# MCU.net
KiCad netlist of a schematic drawn in Altium Designer
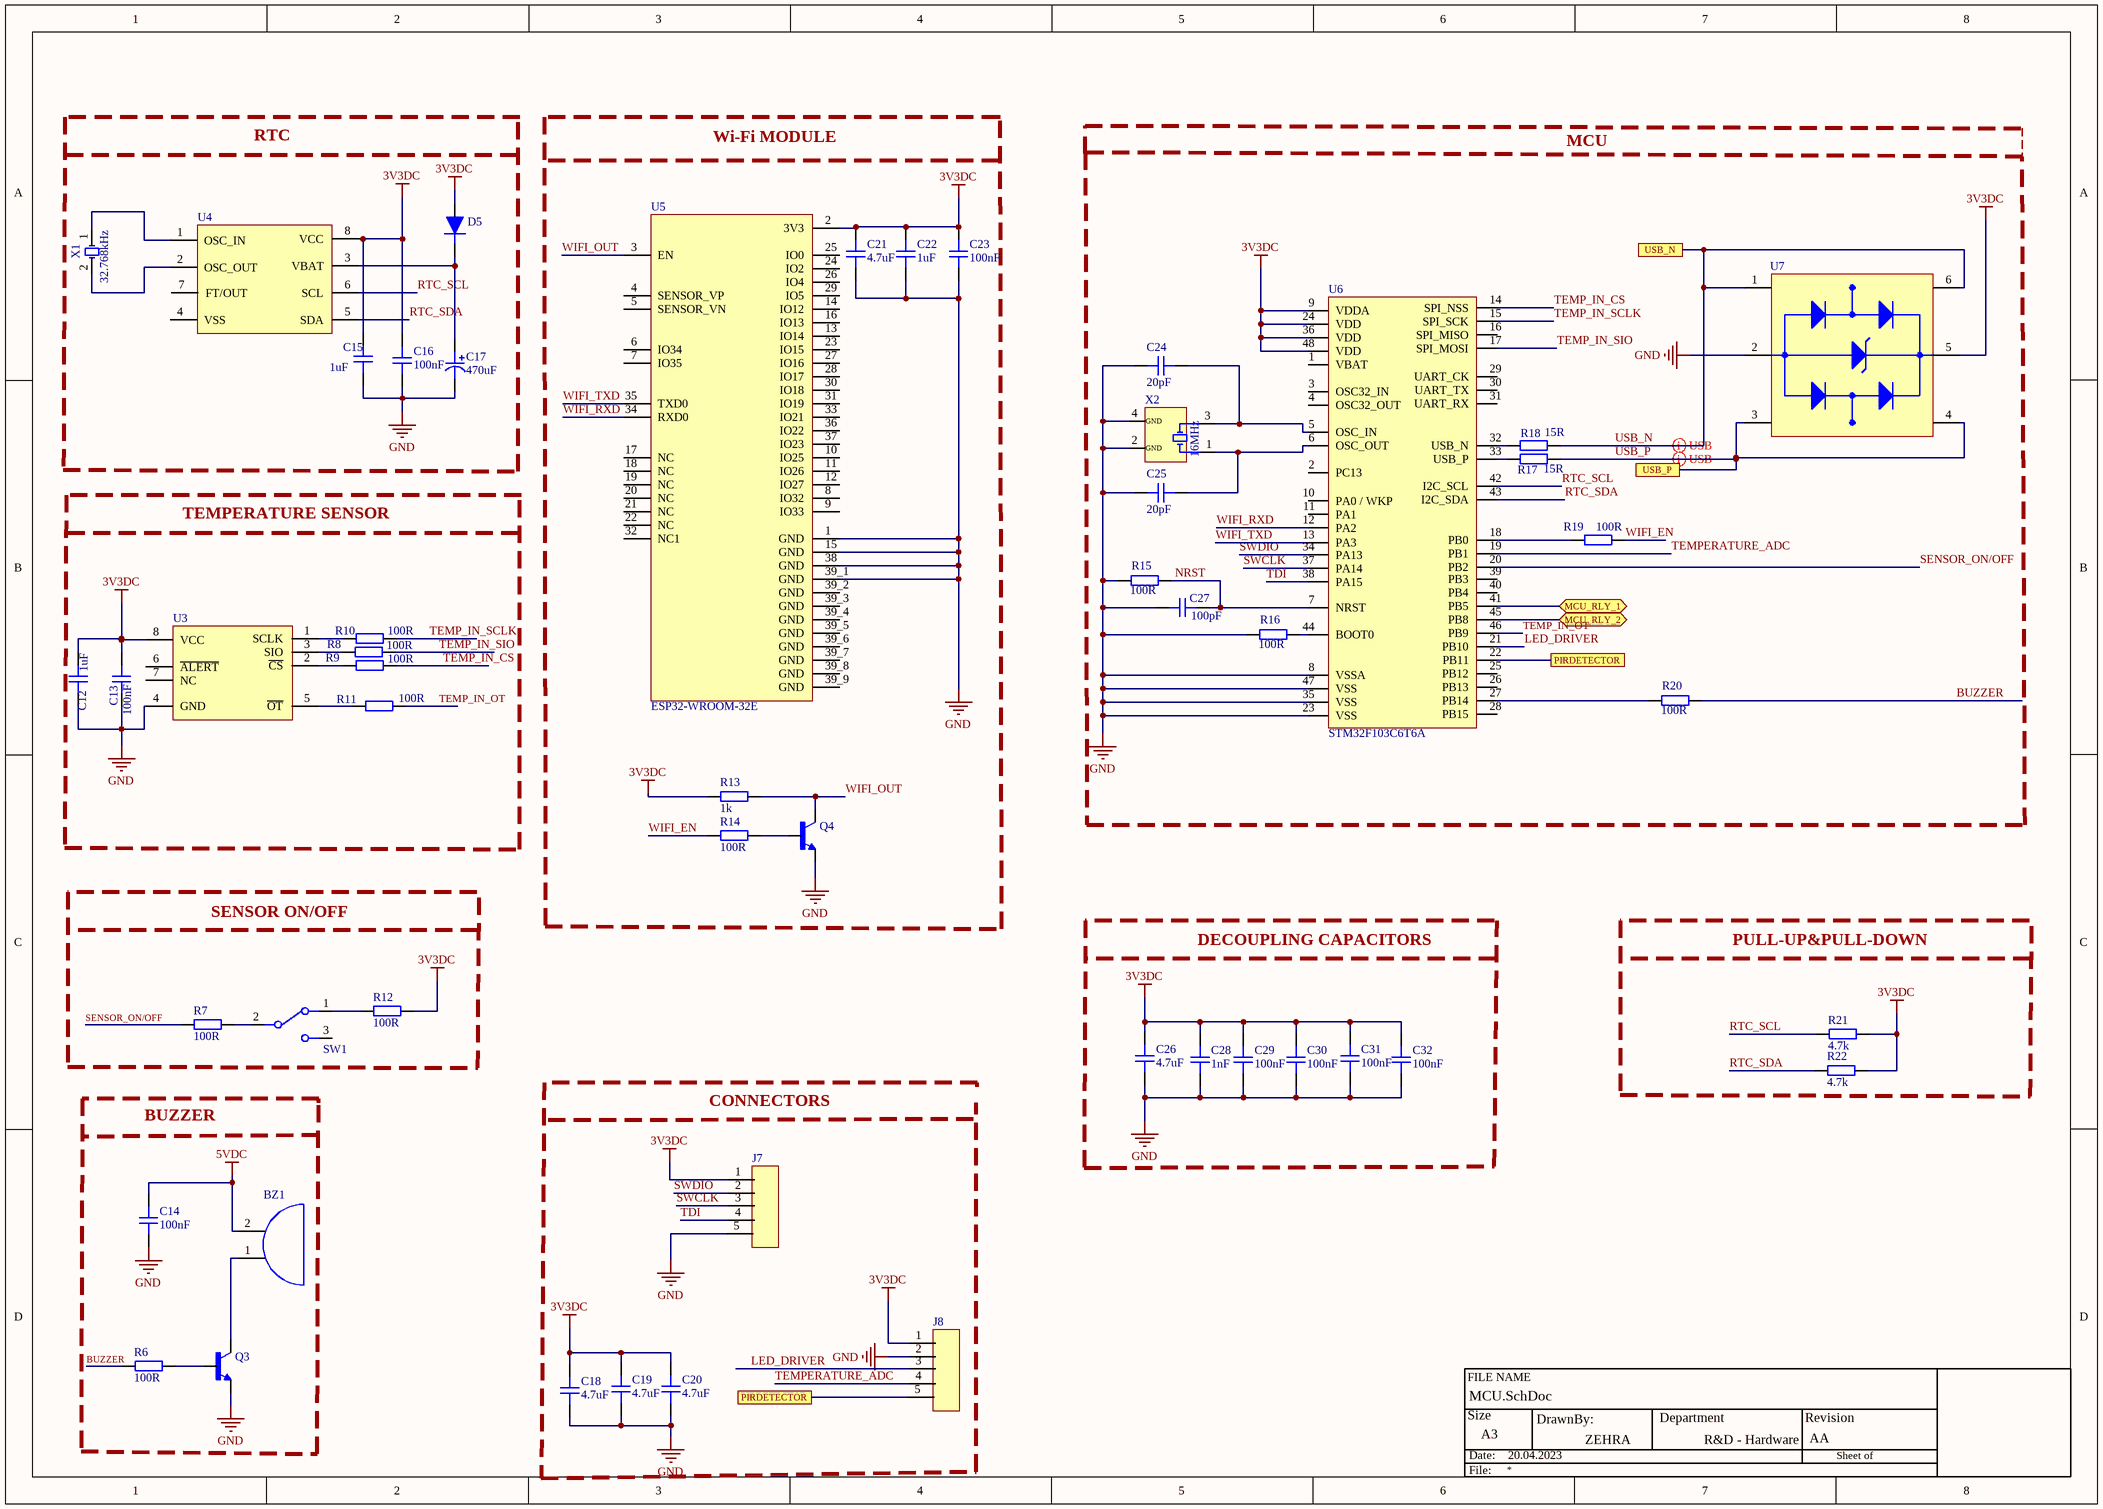
[diagram p0: MCU.SchDoc]

(export (version "E")
  (design (tool "Eeschema 10.0.6"))
  (components
    (comp (ref "BZ1")
      (value "CMI-9605IC-0580T")
      (footprint "CMI-9605IC-0580T")
      (description "Audio Buzzer Magnetic 3VDC 7VDC 30mA 5VDC 85dB 2600Hz to 2800Hz Through Hole Pin Box")
      (fields (field (name "MANUFACTURER") "CUI Devices") (field (name "DESIGNER") "ZehraOzkan"))
      (libsource (lib "Integrated_Library1") (part "CMI-9605IC-0580T"))
    )
    (comp (ref "C12")
      (value "1uF")
      (footprint "CAP_0805")
      (description "Capacitor SMD 0805 10V")
      (fields (field (name "DESIGNER") "ZehraOzkan"))
      (libsource (lib "Integrated_Library1") (part "CAP_0805_10V"))
    )
    (comp (ref "C13")
      (value "100nF")
      (footprint "CAP_0805")
      (description "Capacitor SMD 0805 10V")
      (fields (field (name "DESIGNER") "ZehraOzkan"))
      (libsource (lib "Integrated_Library1") (part "CAP_0805_10V"))
    )
    (comp (ref "C14")
      (value "100nF")
      (footprint "CAP_0805")
      (description "Capacitor SMD 0805 10V")
      (fields (field (name "DESIGNER") "ZehraOzkan"))
      (libsource (lib "Integrated_Library1") (part "CAP_0805_10V"))
    )
    (comp (ref "C15")
      (value "1uF")
      (footprint "CAP_0805")
      (description "Capacitor SMD 0805 10V")
      (fields (field (name "DESIGNER") "ZehraOzkan"))
      (libsource (lib "Integrated_Library1") (part "CAP_0805_10V"))
    )
    (comp (ref "C16")
      (value "100nF")
      (footprint "CAP_0805")
      (description "Capacitor SMD 0805 10V")
      (fields (field (name "DESIGNER") "ZehraOzkan"))
      (libsource (lib "Integrated_Library1") (part "CAP_0805_10V"))
    )
    (comp (ref "C17")
      (value "470uF")
      (footprint "CAP_EEVSERIES")
      (description "Cap Aluminum Lytic 68uF 25V 20% (6.3 X 5.4mm) SMD 240mA 2000h 105C T/R")
      (fields
        (field (name "MANUFACTURER") "KEMET")
        (field (name "MANUFACTURER PART NUMBER") "EEV686M025A9GAA")
        (field (name "DESIGNER") "ZehraOzkan")
      )
      (libsource (lib "Integrated_Library1") (part "CAP_ALU_68uF"))
    )
    (comp (ref "C18")
      (value "4.7uF")
      (footprint "CAP_0603")
      (description "Capacitor SMD 0603 10V")
      (libsource (lib "Integrated_Library1") (part "CAP_0603_10V"))
    )
    (comp (ref "C19")
      (value "4.7uF")
      (footprint "CAP_0603")
      (description "Capacitor SMD 0603 10V")
      (libsource (lib "Integrated_Library1") (part "CAP_0603_10V"))
    )
    (comp (ref "C20")
      (value "4.7uF")
      (footprint "CAP_0603")
      (description "Capacitor SMD 0603 10V")
      (libsource (lib "Integrated_Library1") (part "CAP_0603_10V"))
    )
    (comp (ref "C21")
      (value "4.7uF")
      (footprint "CAP_0805")
      (description "Capacitor SMD 0805 10V")
      (fields (field (name "DESIGNER") "ZehraOzkan"))
      (libsource (lib "Integrated_Library1") (part "CAP_0805_10V"))
    )
    (comp (ref "C22")
      (value "1uF")
      (footprint "CAP_0805")
      (description "Capacitor SMD 0805 10V")
      (fields (field (name "DESIGNER") "ZehraOzkan"))
      (libsource (lib "Integrated_Library1") (part "CAP_0805_10V"))
    )
    (comp (ref "C23")
      (value "100nF")
      (footprint "CAP_0805")
      (description "Capacitor SMD 0805 10V")
      (fields (field (name "DESIGNER") "ZehraOzkan"))
      (libsource (lib "Integrated_Library1") (part "CAP_0805_10V"))
    )
    (comp (ref "C24")
      (value "20pF")
      (footprint "CAP_0603")
      (description "Capacitor SMD 0603 10V")
      (libsource (lib "Integrated_Library1") (part "CAP_0603_10V"))
    )
    (comp (ref "C25")
      (value "20pF")
      (footprint "CAP_0603")
      (description "Capacitor SMD 0603 10V")
      (libsource (lib "Integrated_Library1") (part "CAP_0603_10V"))
    )
    (comp (ref "C26")
      (value "4.7uF")
      (footprint "CAP_0603")
      (description "Capacitor SMD 0603 10V")
      (libsource (lib "Integrated_Library1") (part "CAP_0603_10V"))
    )
    (comp (ref "C27")
      (value "100pF")
      (footprint "CAP_0603")
      (description "Capacitor SMD 0603 10V")
      (libsource (lib "Integrated_Library1") (part "CAP_0603_10V"))
    )
    (comp (ref "C28")
      (value "1nF")
      (footprint "CAP_0603")
      (description "Capacitor SMD 0603 10V")
      (libsource (lib "Integrated_Library1") (part "CAP_0603_10V"))
    )
    (comp (ref "C29")
      (value "100nF")
      (footprint "CAP_0603")
      (description "Capacitor SMD 0603 10V")
      (libsource (lib "Integrated_Library1") (part "CAP_0603_10V"))
    )
    (comp (ref "C30")
      (value "100nF")
      (footprint "CAP_0603")
      (description "Capacitor SMD 0603 10V")
      (libsource (lib "Integrated_Library1") (part "CAP_0603_10V"))
    )
    (comp (ref "C31")
      (value "100nF")
      (footprint "CAP_0603")
      (description "Capacitor SMD 0603 10V")
      (libsource (lib "Integrated_Library1") (part "CAP_0603_10V"))
    )
    (comp (ref "C32")
      (value "100nF")
      (footprint "CAP_0603")
      (description "Capacitor SMD 0603 10V")
      (libsource (lib "Integrated_Library1") (part "CAP_0603_10V"))
    )
    (comp (ref "D5")
      (value "1N5824")
      (footprint "1N5824")
      (description "Diode Schottky 30V 5A 2-Pin Axial Leaded Tray")
      (fields (field (name "MANUFACTURER") "Microsemi") (field (name "DESIGNER") "ZehraOzkan"))
      (libsource (lib "Integrated_Library1") (part "1N5824"))
    )
    (comp (ref "J7")
      (value "Terminal_Block_Header")
      (footprint "HEADER_5")
      (description "5 pin Female")
      (fields (field (name "DESIGNER") "ZehraOzkan"))
      (libsource (lib "Integrated_Library1") (part "Terminal_Block_Header"))
    )
    (comp (ref "J8")
      (value "Terminal_Block_Header")
      (footprint "HEADER_5")
      (description "5 pin Female")
      (fields (field (name "DESIGNER") "ZehraOzkan"))
      (libsource (lib "Integrated_Library1") (part "Terminal_Block_Header"))
    )
    (comp (ref "Q3")
      (value "BC237")
      (footprint "BC237")
      (description "Transistor NPN BC237B MOTOROLA milliampere=100 V=45 R204")
      (fields
        (field (name "MANUFACTURER") "ON Semiconductor / Fairchild")
        (field (name "MANUFACTURER PART NUMBER") "BC237B")
        (field (name "DESIGNER") "ZehraOzkan")
      )
      (libsource (lib "Integrated_Library1") (part "BC237"))
    )
    (comp (ref "Q4")
      (value "BC237")
      (footprint "BC237")
      (description "Transistor NPN BC237B MOTOROLA milliampere=100 V=45 R204")
      (fields
        (field (name "MANUFACTURER") "ON Semiconductor / Fairchild")
        (field (name "MANUFACTURER PART NUMBER") "BC237B")
        (field (name "DESIGNER") "ZehraOzkan")
      )
      (libsource (lib "Integrated_Library1") (part "BC237"))
    )
    (comp (ref "R6")
      (value "100R")
      (footprint "RES_0805")
      (description "Resistor SMD 0805")
      (fields (field (name "DESIGNER") "ZehraOzkan"))
      (libsource (lib "Integrated_Library1") (part "RES_0805"))
    )
    (comp (ref "R7")
      (value "100R")
      (footprint "RES_0805")
      (description "Resistor SMD 0805")
      (fields (field (name "DESIGNER") "ZehraOzkan"))
      (libsource (lib "Integrated_Library1") (part "RES_0805"))
    )
    (comp (ref "R8")
      (value "100R")
      (footprint "RES_0805")
      (description "Resistor SMD 0805")
      (fields (field (name "DESIGNER") "ZehraOzkan"))
      (libsource (lib "Integrated_Library1") (part "RES_0805"))
    )
    (comp (ref "R9")
      (value "100R")
      (footprint "RES_0805")
      (description "Resistor SMD 0805")
      (fields (field (name "DESIGNER") "ZehraOzkan"))
      (libsource (lib "Integrated_Library1") (part "RES_0805"))
    )
    (comp (ref "R10")
      (value "100R")
      (footprint "RES_0805")
      (description "Resistor SMD 0805")
      (fields (field (name "DESIGNER") "ZehraOzkan"))
      (libsource (lib "Integrated_Library1") (part "RES_0805"))
    )
    (comp (ref "R11")
      (value "100R")
      (footprint "RES_0805")
      (description "Resistor SMD 0805")
      (fields (field (name "DESIGNER") "ZehraOzkan"))
      (libsource (lib "Integrated_Library1") (part "RES_0805"))
    )
    (comp (ref "R12")
      (value "100R")
      (footprint "RES_0805")
      (description "Resistor SMD 0805")
      (fields (field (name "DESIGNER") "ZehraOzkan"))
      (libsource (lib "Integrated_Library1") (part "RES_0805"))
    )
    (comp (ref "R13")
      (value "1k")
      (footprint "RES_0805")
      (description "Resistor SMD 0805")
      (fields (field (name "DESIGNER") "ZehraOzkan"))
      (libsource (lib "Integrated_Library1") (part "RES_0805"))
    )
    (comp (ref "R14")
      (value "100R")
      (footprint "RES_0805")
      (description "Resistor SMD 0805")
      (fields (field (name "DESIGNER") "ZehraOzkan"))
      (libsource (lib "Integrated_Library1") (part "RES_0805"))
    )
    (comp (ref "R15")
      (value "100R")
      (footprint "RES_0805")
      (description "Resistor SMD 0805")
      (fields (field (name "DESIGNER") "ZehraOzkan"))
      (libsource (lib "Integrated_Library1") (part "RES_0805"))
    )
    (comp (ref "R16")
      (value "100R")
      (footprint "RES_0805")
      (description "Resistor SMD 0805")
      (fields (field (name "DESIGNER") "ZehraOzkan"))
      (libsource (lib "Integrated_Library1") (part "RES_0805"))
    )
    (comp (ref "R17")
      (value "15R")
      (footprint "RES_0805")
      (description "Resistor SMD 0805")
      (fields (field (name "DESIGNER") "ZehraOzkan"))
      (libsource (lib "Integrated_Library1") (part "RES_0805"))
    )
    (comp (ref "R18")
      (value "15R")
      (footprint "RES_0805")
      (description "Resistor SMD 0805")
      (fields (field (name "DESIGNER") "ZehraOzkan"))
      (libsource (lib "Integrated_Library1") (part "RES_0805"))
    )
    (comp (ref "R19")
      (value "100R")
      (footprint "RES_0805")
      (description "Resistor SMD 0805")
      (fields (field (name "DESIGNER") "ZehraOzkan"))
      (libsource (lib "Integrated_Library1") (part "RES_0805"))
    )
    (comp (ref "R20")
      (value "100R")
      (footprint "RES_0805")
      (description "Resistor SMD 0805")
      (fields (field (name "DESIGNER") "ZehraOzkan"))
      (libsource (lib "Integrated_Library1") (part "RES_0805"))
    )
    (comp (ref "R21")
      (value "4.7k")
      (footprint "RES_0805")
      (description "Resistor SMD 0805")
      (fields (field (name "DESIGNER") "ZehraOzkan"))
      (libsource (lib "Integrated_Library1") (part "RES_0805"))
    )
    (comp (ref "R22")
      (value "4.7k")
      (footprint "RES_0805")
      (description "Resistor SMD 0805")
      (fields (field (name "DESIGNER") "ZehraOzkan"))
      (libsource (lib "Integrated_Library1") (part "RES_0805"))
    )
    (comp (ref "SW1")
      (value "OS102011MA1QN1")
      (footprint "SWITCH")
      (fields (field (name "DESIGNER") "ZehraOzkan"))
      (libsource (lib "Integrated_Library1") (part "Switch"))
    )
    (comp (ref "U3")
      (value "MAX6662")
      (footprint "SOIC-8")
      (description "Temp Sensor Digital Serial (3-Wire, SPI) 8-Pin SOIC N Tube")
      (fields
        (field (name "MANUFACTURER") "Maxim")
        (field (name "MANUFACTURER PART NUMBER") "MAX6662MSA+")
        (field (name "DESIGNER") "ZehraOzkan")
      )
      (libsource (lib "Integrated_Library1") (part "MAX6662"))
    )
    (comp (ref "U4")
      (value "M41T00")
      (footprint "SOIC-8")
      (description "Real-time Clocks Clock/Calendar I2C, 2-Wire Serial 70uA @ 2V ~ 5.5V SOIC-8_150mil RoHS")
      (fields
        (field (name "MANUFACTURER") "STMicroelectronics")
        (field (name "MANUFACTURER PART NUMBER") "M41T00M6F")
        (field (name "DESIGNER") "ZehraOzkan")
      )
      (libsource (lib "Integrated_Library1") (part "M41T00M6F"))
    )
    (comp (ref "U5")
      (value "ESP32-WROOM-32E")
      (footprint "ESP32-WROOM-32E")
      (fields (field (name "MANUFACTURER") "Espressif") (field (name "DESIGNER") "ZehraOzkan"))
      (libsource (lib "Integrated_Library1") (part "ESP32-WROOM-32E"))
    )
    (comp (ref "U6")
      (value "STM32F103C6T6A")
      (footprint "LQFP-48")
      (description "MCU 32-bit STM32F ARM Cortex M3 RISC 32KB Flash 2.5V/3.3V 48-Pin LQFP Tray")
      (fields (field (name "MANUFACTURER") "STMicroelectronics") (field (name "DESIGNER") "ZehraOzkan"))
      (libsource (lib "Integrated_Library1") (part "STM32F103C6T6A"))
    )
    (comp (ref "U7")
      (value "USBLC6-2SC6")
      (footprint "SOT23-6L")
      (description "TVS DIODE 5.25VWM 17VC SOT23-6")
      (fields (field (name "MANUFACTURER") "STMicroelectronics") (field (name "DESIGNER") "ZehraOzkan"))
      (libsource (lib "Integrated_Library1") (part "USB PROTECTION"))
    )
    (comp (ref "X1")
      (value "32.768kHz")
      (footprint "ABS05")
      (description "Crystal 0.032768MHz ±20ppm (Tol) 12.5pF Flexural 90000Ohm 2-Pin CSMD T/R")
      (fields
        (field (name "MANUFACTURER") "Abracon")
        (field (name "MANUFACTURER PART NUMBER") "ABS05-32.768KHZ-T")
        (field (name "DESIGNER") "ZehraOzkan")
      )
      (libsource (lib "Integrated_Library1") (part "Crystal 32768kHz"))
    )
    (comp (ref "X2")
      (value "ECS-160-20-30B-TR")
      (footprint "ECS")
      (description "Crystal 16MHz ±30ppm (Tol) ±50ppm (Stability) 20pF FUND 50Ohm 4-Pin Mini-SMD T/R")
      (fields
        (field (name "MANUFACTURER") "ECS International")
        (field (name "TOLERANCE") "50ppm")
        (field (name "FREQUENCY") "16MHz")
        (field (name "DESIGNER") "ZehraOzkan")
      )
      (libsource (lib "Integrated_Library1") (part "Crystal 16MHz"))
    )
  )
  (nets
    (net (code "1") (name "/BUZZER") (class "Default")
      (node (ref "R20") (pin "2") (pinfunction "2_2") (pintype "passive"))
      (node (ref "R6") (pin "1") (pinfunction "1_1") (pintype "passive"))
    )
    (net (code "2") (name "/LED_DRIVER") (class "Default")
      (node (ref "J8") (pin "3") (pinfunction "3_3") (pintype "passive"))
      (node (ref "U6") (pin "21") (pinfunction "PB10_21") (pintype "passive"))
    )
    (net (code "3") (name "/MCU_RLY_1") (class "Default")
      (node (ref "U6") (pin "41") (pinfunction "PB5_41") (pintype "passive"))
    )
    (net (code "4") (name "/MCU_RLY_2") (class "Default")
      (node (ref "U6") (pin "45") (pinfunction "PB8_45") (pintype "passive"))
    )
    (net (code "5") (name "/NRST") (class "Default")
      (node (ref "C27") (pin "2") (pinfunction "2_2") (pintype "passive"))
      (node (ref "R15") (pin "2") (pinfunction "2_2") (pintype "passive"))
      (node (ref "U6") (pin "7") (pinfunction "NRST_7") (pintype "passive"))
    )
    (net (code "6") (name "/PIRDETECTOR") (class "Default")
      (node (ref "J8") (pin "5") (pinfunction "5_5") (pintype "passive"))
      (node (ref "U6") (pin "22") (pinfunction "PB11_22") (pintype "passive"))
    )
    (net (code "7") (name "/RTC_SCL") (class "Default")
      (node (ref "R21") (pin "1") (pinfunction "1_1") (pintype "passive"))
      (node (ref "U4") (pin "6") (pinfunction "SCL_6") (pintype "passive"))
      (node (ref "U6") (pin "42") (pinfunction "I2C_SCL_42") (pintype "passive"))
    )
    (net (code "8") (name "/RTC_SDA") (class "Default")
      (node (ref "R22") (pin "1") (pinfunction "1_1") (pintype "passive"))
      (node (ref "U4") (pin "5") (pinfunction "SDA_5") (pintype "passive"))
      (node (ref "U6") (pin "43") (pinfunction "I2C_SDA_43") (pintype "passive"))
    )
    (net (code "9") (name "/SENSOR_ON{slash}OFF") (class "Default")
      (node (ref "R7") (pin "1") (pinfunction "1_1") (pintype "passive"))
      (node (ref "U6") (pin "20") (pinfunction "PB2_20") (pintype "passive"))
    )
    (net (code "10") (name "/SWCLK") (class "Default")
      (node (ref "J7") (pin "3") (pinfunction "3_3") (pintype "passive"))
      (node (ref "U6") (pin "37") (pinfunction "PA14_37") (pintype "passive"))
    )
    (net (code "11") (name "/SWDIO") (class "Default")
      (node (ref "J7") (pin "2") (pinfunction "2_2") (pintype "passive"))
      (node (ref "U6") (pin "34") (pinfunction "PA13_34") (pintype "passive"))
    )
    (net (code "12") (name "/TDI") (class "Default")
      (node (ref "J7") (pin "4") (pinfunction "4_4") (pintype "passive"))
      (node (ref "U6") (pin "38") (pinfunction "PA15_38") (pintype "passive"))
    )
    (net (code "13") (name "/TEMPERATURE_ADC") (class "Default")
      (node (ref "J8") (pin "4") (pinfunction "4_4") (pintype "passive"))
      (node (ref "U6") (pin "19") (pinfunction "PB1_19") (pintype "passive"))
    )
    (net (code "14") (name "/TEMP_IN_CS") (class "Default")
      (node (ref "R9") (pin "2") (pinfunction "2_2") (pintype "passive"))
      (node (ref "U6") (pin "14") (pinfunction "SPI_NSS_14") (pintype "passive"))
    )
    (net (code "15") (name "/TEMP_IN_OT") (class "Default")
      (node (ref "R11") (pin "2") (pinfunction "2_2") (pintype "passive"))
      (node (ref "U6") (pin "46") (pinfunction "PB9_46") (pintype "passive"))
    )
    (net (code "16") (name "/TEMP_IN_SCLK") (class "Default")
      (node (ref "R10") (pin "2") (pinfunction "2_2") (pintype "passive"))
      (node (ref "U6") (pin "15") (pinfunction "SPI_SCK_15") (pintype "passive"))
    )
    (net (code "17") (name "/TEMP_IN_SIO") (class "Default")
      (node (ref "R8") (pin "2") (pinfunction "2_2") (pintype "passive"))
      (node (ref "U6") (pin "17") (pinfunction "SPI_MOSI_17") (pintype "passive"))
    )
    (net (code "18") (name "/USB_N") (class "Default")
      (node (ref "R18") (pin "2") (pinfunction "2_2") (pintype "passive"))
      (node (ref "U7") (pin "1") (pinfunction "I/O1_IN_1") (pintype "passive"))
      (node (ref "U7") (pin "6") (pinfunction "I/O1_OUT_6") (pintype "passive"))
    )
    (net (code "19") (name "/USB_P") (class "Default")
      (node (ref "R17") (pin "2") (pinfunction "2_2") (pintype "passive"))
      (node (ref "U7") (pin "3") (pinfunction "I/O2_IN_3") (pintype "passive"))
      (node (ref "U7") (pin "4") (pinfunction "I/O2_OUT_4") (pintype "passive"))
    )
    (net (code "20") (name "/WIFI_EN") (class "Default")
      (node (ref "R14") (pin "1") (pinfunction "1_1") (pintype "passive"))
      (node (ref "R19") (pin "2") (pinfunction "2_2") (pintype "passive"))
    )
    (net (code "21") (name "/WIFI_OUT") (class "Default")
      (node (ref "Q4") (pin "3") (pinfunction "C_3") (pintype "passive"))
      (node (ref "R13") (pin "2") (pinfunction "2_2") (pintype "passive"))
      (node (ref "U5") (pin "3") (pinfunction "EN_3") (pintype "passive"))
    )
    (net (code "22") (name "/WIFI_RXD") (class "Default")
      (node (ref "U5") (pin "34") (pinfunction "RXD0_34") (pintype "passive"))
      (node (ref "U6") (pin "12") (pinfunction "PA2_12") (pintype "passive"))
    )
    (net (code "23") (name "/WIFI_TXD") (class "Default")
      (node (ref "U5") (pin "35") (pinfunction "TXD0_35") (pintype "passive"))
      (node (ref "U6") (pin "13") (pinfunction "PA3_13") (pintype "passive"))
    )
    (net (code "24") (name "3V3DC") (class "Default")
      (node (ref "C12") (pin "2") (pinfunction "2_2") (pintype "passive"))
      (node (ref "C13") (pin "2") (pinfunction "2_2") (pintype "passive"))
      (node (ref "C15") (pin "2") (pinfunction "2_2") (pintype "passive"))
      (node (ref "C16") (pin "2") (pinfunction "2_2") (pintype "passive"))
      (node (ref "C18") (pin "2") (pinfunction "2_2") (pintype "passive"))
      (node (ref "C19") (pin "2") (pinfunction "2_2") (pintype "passive"))
      (node (ref "C20") (pin "2") (pinfunction "2_2") (pintype "passive"))
      (node (ref "C21") (pin "2") (pinfunction "2_2") (pintype "passive"))
      (node (ref "C22") (pin "2") (pinfunction "2_2") (pintype "passive"))
      (node (ref "C23") (pin "2") (pinfunction "2_2") (pintype "passive"))
      (node (ref "C26") (pin "2") (pinfunction "2_2") (pintype "passive"))
      (node (ref "C28") (pin "2") (pinfunction "2_2") (pintype "passive"))
      (node (ref "C29") (pin "2") (pinfunction "2_2") (pintype "passive"))
      (node (ref "C30") (pin "2") (pinfunction "2_2") (pintype "passive"))
      (node (ref "C31") (pin "2") (pinfunction "2_2") (pintype "passive"))
      (node (ref "C32") (pin "2") (pinfunction "2_2") (pintype "passive"))
      (node (ref "D5") (pin "1") (pinfunction "A_1") (pintype "passive"))
      (node (ref "J7") (pin "1") (pinfunction "1_1") (pintype "passive"))
      (node (ref "J8") (pin "1") (pinfunction "1_1") (pintype "passive"))
      (node (ref "R12") (pin "2") (pinfunction "2_2") (pintype "passive"))
      (node (ref "R13") (pin "1") (pinfunction "1_1") (pintype "passive"))
      (node (ref "R21") (pin "2") (pinfunction "2_2") (pintype "passive"))
      (node (ref "R22") (pin "2") (pinfunction "2_2") (pintype "passive"))
      (node (ref "U3") (pin "8") (pinfunction "VCC_8") (pintype "passive"))
      (node (ref "U4") (pin "8") (pinfunction "VCC_8") (pintype "passive"))
      (node (ref "U5") (pin "2") (pinfunction "3V3_2") (pintype "power_in"))
      (node (ref "U6") (pin "24") (pinfunction "VDD_24") (pintype "passive"))
      (node (ref "U6") (pin "36") (pinfunction "VDD_36") (pintype "passive"))
      (node (ref "U6") (pin "48") (pinfunction "VDD_48") (pintype "passive"))
      (node (ref "U6") (pin "9") (pinfunction "VDDA_9") (pintype "passive"))
      (node (ref "U7") (pin "5") (pinfunction "VBUS_5") (pintype "passive"))
    )
    (net (code "25") (name "5VDC") (class "Default")
      (node (ref "BZ1") (pin "2") (pinfunction "2_2") (pintype "passive"))
      (node (ref "C14") (pin "2") (pinfunction "2_2") (pintype "passive"))
    )
    (net (code "26") (name "GND") (class "Default")
      (node (ref "C12") (pin "1") (pinfunction "1_1") (pintype "passive"))
      (node (ref "C13") (pin "1") (pinfunction "1_1") (pintype "passive"))
      (node (ref "C14") (pin "1") (pinfunction "1_1") (pintype "passive"))
      (node (ref "C15") (pin "1") (pinfunction "1_1") (pintype "passive"))
      (node (ref "C16") (pin "1") (pinfunction "1_1") (pintype "passive"))
      (node (ref "C17") (pin "2") (pinfunction "2_2") (pintype "passive"))
      (node (ref "C18") (pin "1") (pinfunction "1_1") (pintype "passive"))
      (node (ref "C19") (pin "1") (pinfunction "1_1") (pintype "passive"))
      (node (ref "C20") (pin "1") (pinfunction "1_1") (pintype "passive"))
      (node (ref "C21") (pin "1") (pinfunction "1_1") (pintype "passive"))
      (node (ref "C22") (pin "1") (pinfunction "1_1") (pintype "passive"))
      (node (ref "C23") (pin "1") (pinfunction "1_1") (pintype "passive"))
      (node (ref "C24") (pin "1") (pinfunction "1_1") (pintype "passive"))
      (node (ref "C25") (pin "1") (pinfunction "1_1") (pintype "passive"))
      (node (ref "C26") (pin "1") (pinfunction "1_1") (pintype "passive"))
      (node (ref "C27") (pin "1") (pinfunction "1_1") (pintype "passive"))
      (node (ref "C28") (pin "1") (pinfunction "1_1") (pintype "passive"))
      (node (ref "C29") (pin "1") (pinfunction "1_1") (pintype "passive"))
      (node (ref "C30") (pin "1") (pinfunction "1_1") (pintype "passive"))
      (node (ref "C31") (pin "1") (pinfunction "1_1") (pintype "passive"))
      (node (ref "C32") (pin "1") (pinfunction "1_1") (pintype "passive"))
      (node (ref "J7") (pin "5") (pinfunction "5_5") (pintype "passive"))
      (node (ref "J8") (pin "2") (pinfunction "2_2") (pintype "passive"))
      (node (ref "Q3") (pin "1") (pinfunction "E_1") (pintype "passive"))
      (node (ref "Q4") (pin "1") (pinfunction "E_1") (pintype "passive"))
      (node (ref "R15") (pin "1") (pinfunction "1_1") (pintype "passive"))
      (node (ref "R16") (pin "1") (pinfunction "1_1") (pintype "passive"))
      (node (ref "U3") (pin "4") (pinfunction "GND_4") (pintype "power_in"))
      (node (ref "U5") (pin "1") (pinfunction "GND_1") (pintype "power_in"))
      (node (ref "U5") (pin "15") (pinfunction "GND_15") (pintype "power_in"))
      (node (ref "U5") (pin "38") (pinfunction "GND_38") (pintype "power_in"))
      (node (ref "U5") (pin "39_1") (pinfunction "GND_39_1") (pintype "power_in"))
      (node (ref "U6") (pin "23") (pinfunction "VSS_23") (pintype "passive"))
      (node (ref "U6") (pin "35") (pinfunction "VSS_35") (pintype "passive"))
      (node (ref "U6") (pin "47") (pinfunction "VSS_47") (pintype "passive"))
      (node (ref "U6") (pin "8") (pinfunction "VSSA_8") (pintype "passive"))
      (node (ref "U7") (pin "2") (pinfunction "GND_2") (pintype "passive"))
      (node (ref "X2") (pin "2") (pinfunction "GND_2") (pintype "passive"))
      (node (ref "X2") (pin "4") (pinfunction "GND_4") (pintype "passive"))
    )
    (net (code "27") (name "Net-(D5-K)") (class "Default")
      (node (ref "C17") (pin "1") (pinfunction "1_1") (pintype "passive"))
      (node (ref "D5") (pin "2") (pinfunction "K_2") (pintype "passive"))
      (node (ref "U4") (pin "3") (pinfunction "VBAT_3") (pintype "passive"))
    )
    (net (code "28") (name "Net-(Q3-B)") (class "Default")
      (node (ref "Q3") (pin "2") (pinfunction "B_2") (pintype "passive"))
      (node (ref "R6") (pin "2") (pinfunction "2_2") (pintype "passive"))
    )
    (net (code "29") (name "Net-(Q3-C)") (class "Default")
      (node (ref "BZ1") (pin "1") (pinfunction "1_1") (pintype "passive"))
      (node (ref "Q3") (pin "3") (pinfunction "C_3") (pintype "passive"))
    )
    (net (code "30") (name "Net-(Q4-B)") (class "Default")
      (node (ref "Q4") (pin "2") (pinfunction "B_2") (pintype "passive"))
      (node (ref "R14") (pin "2") (pinfunction "2_2") (pintype "passive"))
    )
    (net (code "31") (name "Net-(R12-Pad1)") (class "Default")
      (node (ref "R12") (pin "1") (pinfunction "1_1") (pintype "passive"))
      (node (ref "SW1") (pin "1") (pinfunction "1_1") (pintype "passive"))
    )
    (net (code "32") (name "Net-(SW1-COM)") (class "Default")
      (node (ref "R7") (pin "2") (pinfunction "2_2") (pintype "passive"))
      (node (ref "SW1") (pin "2") (pinfunction "COM_2") (pintype "passive"))
    )
    (net (code "33") (name "Net-(U3-SCLK)") (class "Default")
      (node (ref "R10") (pin "1") (pinfunction "1_1") (pintype "passive"))
      (node (ref "U3") (pin "1") (pinfunction "SCLK_1") (pintype "passive"))
    )
    (net (code "34") (name "Net-(U3-SIO)") (class "Default")
      (node (ref "R8") (pin "1") (pinfunction "1_1") (pintype "passive"))
      (node (ref "U3") (pin "3") (pinfunction "SIO_3") (pintype "passive"))
    )
    (net (code "35") (name "Net-(U3-~{CS})") (class "Default")
      (node (ref "R9") (pin "1") (pinfunction "1_1") (pintype "passive"))
      (node (ref "U3") (pin "2") (pinfunction "~{CS}_2") (pintype "passive"))
    )
    (net (code "36") (name "Net-(U3-~{OT})") (class "Default")
      (node (ref "R11") (pin "1") (pinfunction "1_1") (pintype "passive"))
      (node (ref "U3") (pin "5") (pinfunction "~{OT}_5") (pintype "passive"))
    )
    (net (code "37") (name "Net-(U4-OSC_IN)") (class "Default")
      (node (ref "U4") (pin "1") (pinfunction "OSC_IN_1") (pintype "passive"))
      (node (ref "X1") (pin "1") (pintype "passive"))
    )
    (net (code "38") (name "Net-(U4-OSC_OUT)") (class "Default")
      (node (ref "U4") (pin "2") (pinfunction "OSC_OUT_2") (pintype "passive"))
      (node (ref "X1") (pin "2") (pintype "passive"))
    )
    (net (code "39") (name "Net-(U6-BOOT0)") (class "Default")
      (node (ref "R16") (pin "2") (pinfunction "2_2") (pintype "passive"))
      (node (ref "U6") (pin "44") (pinfunction "BOOT0_44") (pintype "passive"))
    )
    (net (code "40") (name "Net-(U6-OSC_IN)") (class "Default")
      (node (ref "C24") (pin "2") (pinfunction "2_2") (pintype "passive"))
      (node (ref "U6") (pin "5") (pinfunction "OSC_IN_5") (pintype "passive"))
      (node (ref "X2") (pin "3") (pinfunction "3_3") (pintype "passive"))
    )
    (net (code "41") (name "Net-(U6-OSC_OUT)") (class "Default")
      (node (ref "C25") (pin "2") (pinfunction "2_2") (pintype "passive"))
      (node (ref "U6") (pin "6") (pinfunction "OSC_OUT_6") (pintype "passive"))
      (node (ref "X2") (pin "1") (pinfunction "1_1") (pintype "passive"))
    )
    (net (code "42") (name "Net-(U6-PB0)") (class "Default")
      (node (ref "R19") (pin "1") (pinfunction "1_1") (pintype "passive"))
      (node (ref "U6") (pin "18") (pinfunction "PB0_18") (pintype "passive"))
    )
    (net (code "43") (name "Net-(U6-PB14)") (class "Default")
      (node (ref "R20") (pin "1") (pinfunction "1_1") (pintype "passive"))
      (node (ref "U6") (pin "27") (pinfunction "PB14_27") (pintype "passive"))
    )
    (net (code "44") (name "Net-(U6-USB_N)") (class "Default")
      (node (ref "R18") (pin "1") (pinfunction "1_1") (pintype "passive"))
      (node (ref "U6") (pin "32") (pinfunction "USB_N_32") (pintype "passive"))
    )
    (net (code "45") (name "Net-(U6-USB_P)") (class "Default")
      (node (ref "R17") (pin "1") (pinfunction "1_1") (pintype "passive"))
      (node (ref "U6") (pin "33") (pinfunction "USB_P_33") (pintype "passive"))
    )
    (net (code "46") (name "unconnected-(SW1-Pad3)") (class "Default")
      (node (ref "SW1") (pin "3") (pinfunction "3_3") (pintype "passive"))
    )
    (net (code "47") (name "unconnected-(U3-NC-Pad7)") (class "Default")
      (node (ref "U3") (pin "7") (pinfunction "NC_7") (pintype "passive"))
    )
    (net (code "48") (name "unconnected-(U3-~{ALERT}-Pad6)") (class "Default")
      (node (ref "U3") (pin "6") (pinfunction "~{ALERT}_6") (pintype "passive"))
    )
    (net (code "49") (name "unconnected-(U4-FT{slash}OUT-Pad7)") (class "Default")
      (node (ref "U4") (pin "7") (pinfunction "FT/OUT_7") (pintype "passive"))
    )
    (net (code "50") (name "unconnected-(U4-VSS-Pad4)") (class "Default")
      (node (ref "U4") (pin "4") (pinfunction "VSS_4") (pintype "power_in"))
    )
    (net (code "51") (name "unconnected-(U5-GND-Pad39_2)") (class "Default")
      (node (ref "U5") (pin "39_2") (pinfunction "GND_39_2") (pintype "power_in"))
    )
    (net (code "52") (name "unconnected-(U5-GND-Pad39_3)") (class "Default")
      (node (ref "U5") (pin "39_3") (pinfunction "GND_39_3") (pintype "power_in"))
    )
    (net (code "53") (name "unconnected-(U5-GND-Pad39_4)") (class "Default")
      (node (ref "U5") (pin "39_4") (pinfunction "GND_39_4") (pintype "power_in"))
    )
    (net (code "54") (name "unconnected-(U5-GND-Pad39_5)") (class "Default")
      (node (ref "U5") (pin "39_5") (pinfunction "GND_39_5") (pintype "power_in"))
    )
    (net (code "55") (name "unconnected-(U5-GND-Pad39_6)") (class "Default")
      (node (ref "U5") (pin "39_6") (pinfunction "GND_39_6") (pintype "power_in"))
    )
    (net (code "56") (name "unconnected-(U5-GND-Pad39_7)") (class "Default")
      (node (ref "U5") (pin "39_7") (pinfunction "GND_39_7") (pintype "power_in"))
    )
    (net (code "57") (name "unconnected-(U5-GND-Pad39_8)") (class "Default")
      (node (ref "U5") (pin "39_8") (pinfunction "GND_39_8") (pintype "power_in"))
    )
    (net (code "58") (name "unconnected-(U5-GND-Pad39_9)") (class "Default")
      (node (ref "U5") (pin "39_9") (pinfunction "GND_39_9") (pintype "power_in"))
    )
    (net (code "59") (name "unconnected-(U5-IO0-Pad25)") (class "Default")
      (node (ref "U5") (pin "25") (pinfunction "IO0_25") (pintype "passive"))
    )
    (net (code "60") (name "unconnected-(U5-IO2-Pad24)") (class "Default")
      (node (ref "U5") (pin "24") (pinfunction "IO2_24") (pintype "passive"))
    )
    (net (code "61") (name "unconnected-(U5-IO4-Pad26)") (class "Default")
      (node (ref "U5") (pin "26") (pinfunction "IO4_26") (pintype "passive"))
    )
    (net (code "62") (name "unconnected-(U5-IO5-Pad29)") (class "Default")
      (node (ref "U5") (pin "29") (pinfunction "IO5_29") (pintype "passive"))
    )
    (net (code "63") (name "unconnected-(U5-IO12-Pad14)") (class "Default")
      (node (ref "U5") (pin "14") (pinfunction "IO12_14") (pintype "passive"))
    )
    (net (code "64") (name "unconnected-(U5-IO13-Pad16)") (class "Default")
      (node (ref "U5") (pin "16") (pinfunction "IO13_16") (pintype "passive"))
    )
    (net (code "65") (name "unconnected-(U5-IO14-Pad13)") (class "Default")
      (node (ref "U5") (pin "13") (pinfunction "IO14_13") (pintype "passive"))
    )
    (net (code "66") (name "unconnected-(U5-IO15-Pad23)") (class "Default")
      (node (ref "U5") (pin "23") (pinfunction "IO15_23") (pintype "passive"))
    )
    (net (code "67") (name "unconnected-(U5-IO16-Pad27)") (class "Default")
      (node (ref "U5") (pin "27") (pinfunction "IO16_27") (pintype "passive"))
    )
    (net (code "68") (name "unconnected-(U5-IO17-Pad28)") (class "Default")
      (node (ref "U5") (pin "28") (pinfunction "IO17_28") (pintype "passive"))
    )
    (net (code "69") (name "unconnected-(U5-IO18-Pad30)") (class "Default")
      (node (ref "U5") (pin "30") (pinfunction "IO18_30") (pintype "passive"))
    )
    (net (code "70") (name "unconnected-(U5-IO19-Pad31)") (class "Default")
      (node (ref "U5") (pin "31") (pinfunction "IO19_31") (pintype "passive"))
    )
    (net (code "71") (name "unconnected-(U5-IO21-Pad33)") (class "Default")
      (node (ref "U5") (pin "33") (pinfunction "IO21_33") (pintype "passive"))
    )
    (net (code "72") (name "unconnected-(U5-IO22-Pad36)") (class "Default")
      (node (ref "U5") (pin "36") (pinfunction "IO22_36") (pintype "passive"))
    )
    (net (code "73") (name "unconnected-(U5-IO23-Pad37)") (class "Default")
      (node (ref "U5") (pin "37") (pinfunction "IO23_37") (pintype "passive"))
    )
    (net (code "74") (name "unconnected-(U5-IO25-Pad10)") (class "Default")
      (node (ref "U5") (pin "10") (pinfunction "IO25_10") (pintype "passive"))
    )
    (net (code "75") (name "unconnected-(U5-IO26-Pad11)") (class "Default")
      (node (ref "U5") (pin "11") (pinfunction "IO26_11") (pintype "passive"))
    )
    (net (code "76") (name "unconnected-(U5-IO27-Pad12)") (class "Default")
      (node (ref "U5") (pin "12") (pinfunction "IO27_12") (pintype "passive"))
    )
    (net (code "77") (name "unconnected-(U5-IO32-Pad8)") (class "Default")
      (node (ref "U5") (pin "8") (pinfunction "IO32_8") (pintype "passive"))
    )
    (net (code "78") (name "unconnected-(U5-IO33-Pad9)") (class "Default")
      (node (ref "U5") (pin "9") (pinfunction "IO33_9") (pintype "passive"))
    )
    (net (code "79") (name "unconnected-(U5-IO34-Pad6)") (class "Default")
      (node (ref "U5") (pin "6") (pinfunction "IO34_6") (pintype "passive"))
    )
    (net (code "80") (name "unconnected-(U5-IO35-Pad7)") (class "Default")
      (node (ref "U5") (pin "7") (pinfunction "IO35_7") (pintype "passive"))
    )
    (net (code "81") (name "unconnected-(U5-NC-Pad17)") (class "Default")
      (node (ref "U5") (pin "17") (pinfunction "NC_17") (pintype "passive"))
    )
    (net (code "82") (name "unconnected-(U5-NC-Pad18)") (class "Default")
      (node (ref "U5") (pin "18") (pinfunction "NC_18") (pintype "passive"))
    )
    (net (code "83") (name "unconnected-(U5-NC-Pad19)") (class "Default")
      (node (ref "U5") (pin "19") (pinfunction "NC_19") (pintype "passive"))
    )
    (net (code "84") (name "unconnected-(U5-NC-Pad20)") (class "Default")
      (node (ref "U5") (pin "20") (pinfunction "NC_20") (pintype "passive"))
    )
    (net (code "85") (name "unconnected-(U5-NC-Pad21)") (class "Default")
      (node (ref "U5") (pin "21") (pinfunction "NC_21") (pintype "passive"))
    )
    (net (code "86") (name "unconnected-(U5-NC-Pad22)") (class "Default")
      (node (ref "U5") (pin "22") (pinfunction "NC_22") (pintype "passive"))
    )
    (net (code "87") (name "unconnected-(U5-NC1-Pad32)") (class "Default")
      (node (ref "U5") (pin "32") (pinfunction "NC1_32") (pintype "passive"))
    )
    (net (code "88") (name "unconnected-(U5-SENSOR_VN-Pad5)") (class "Default")
      (node (ref "U5") (pin "5") (pinfunction "SENSOR_VN_5") (pintype "passive"))
    )
    (net (code "89") (name "unconnected-(U5-SENSOR_VP-Pad4)") (class "Default")
      (node (ref "U5") (pin "4") (pinfunction "SENSOR_VP_4") (pintype "passive"))
    )
    (net (code "90") (name "unconnected-(U6-OSC32_IN-Pad3)") (class "Default")
      (node (ref "U6") (pin "3") (pinfunction "OSC32_IN_3") (pintype "passive"))
    )
    (net (code "91") (name "unconnected-(U6-OSC32_OUT-Pad4)") (class "Default")
      (node (ref "U6") (pin "4") (pinfunction "OSC32_OUT_4") (pintype "passive"))
    )
    (net (code "92") (name "unconnected-(U6-PA0_{slash}_WKP-Pad10)") (class "Default")
      (node (ref "U6") (pin "10") (pinfunction "PA0_/_WKP_10") (pintype "passive"))
    )
    (net (code "93") (name "unconnected-(U6-PA1-Pad11)") (class "Default")
      (node (ref "U6") (pin "11") (pinfunction "PA1_11") (pintype "passive"))
    )
    (net (code "94") (name "unconnected-(U6-PB3-Pad39)") (class "Default")
      (node (ref "U6") (pin "39") (pinfunction "PB3_39") (pintype "passive"))
    )
    (net (code "95") (name "unconnected-(U6-PB4-Pad40)") (class "Default")
      (node (ref "U6") (pin "40") (pinfunction "PB4_40") (pintype "passive"))
    )
    (net (code "96") (name "unconnected-(U6-PB12-Pad25)") (class "Default")
      (node (ref "U6") (pin "25") (pinfunction "PB12_25") (pintype "passive"))
    )
    (net (code "97") (name "unconnected-(U6-PB13-Pad26)") (class "Default")
      (node (ref "U6") (pin "26") (pinfunction "PB13_26") (pintype "passive"))
    )
    (net (code "98") (name "unconnected-(U6-PB15-Pad28)") (class "Default")
      (node (ref "U6") (pin "28") (pinfunction "PB15_28") (pintype "passive"))
    )
    (net (code "99") (name "unconnected-(U6-PC13-Pad2)") (class "Default")
      (node (ref "U6") (pin "2") (pinfunction "PC13_2") (pintype "passive"))
    )
    (net (code "100") (name "unconnected-(U6-SPI_MISO-Pad16)") (class "Default")
      (node (ref "U6") (pin "16") (pinfunction "SPI_MISO_16") (pintype "passive"))
    )
    (net (code "101") (name "unconnected-(U6-UART_CK-Pad29)") (class "Default")
      (node (ref "U6") (pin "29") (pinfunction "UART_CK_29") (pintype "passive"))
    )
    (net (code "102") (name "unconnected-(U6-UART_RX-Pad31)") (class "Default")
      (node (ref "U6") (pin "31") (pinfunction "UART_RX_31") (pintype "passive"))
    )
    (net (code "103") (name "unconnected-(U6-UART_TX-Pad30)") (class "Default")
      (node (ref "U6") (pin "30") (pinfunction "UART_TX_30") (pintype "passive"))
    )
    (net (code "104") (name "unconnected-(U6-VBAT-Pad1)") (class "Default")
      (node (ref "U6") (pin "1") (pinfunction "VBAT_1") (pintype "passive"))
    )
  )
)
